# tokyo.net
KiCad netlist of a schematic drawn in EAGLE
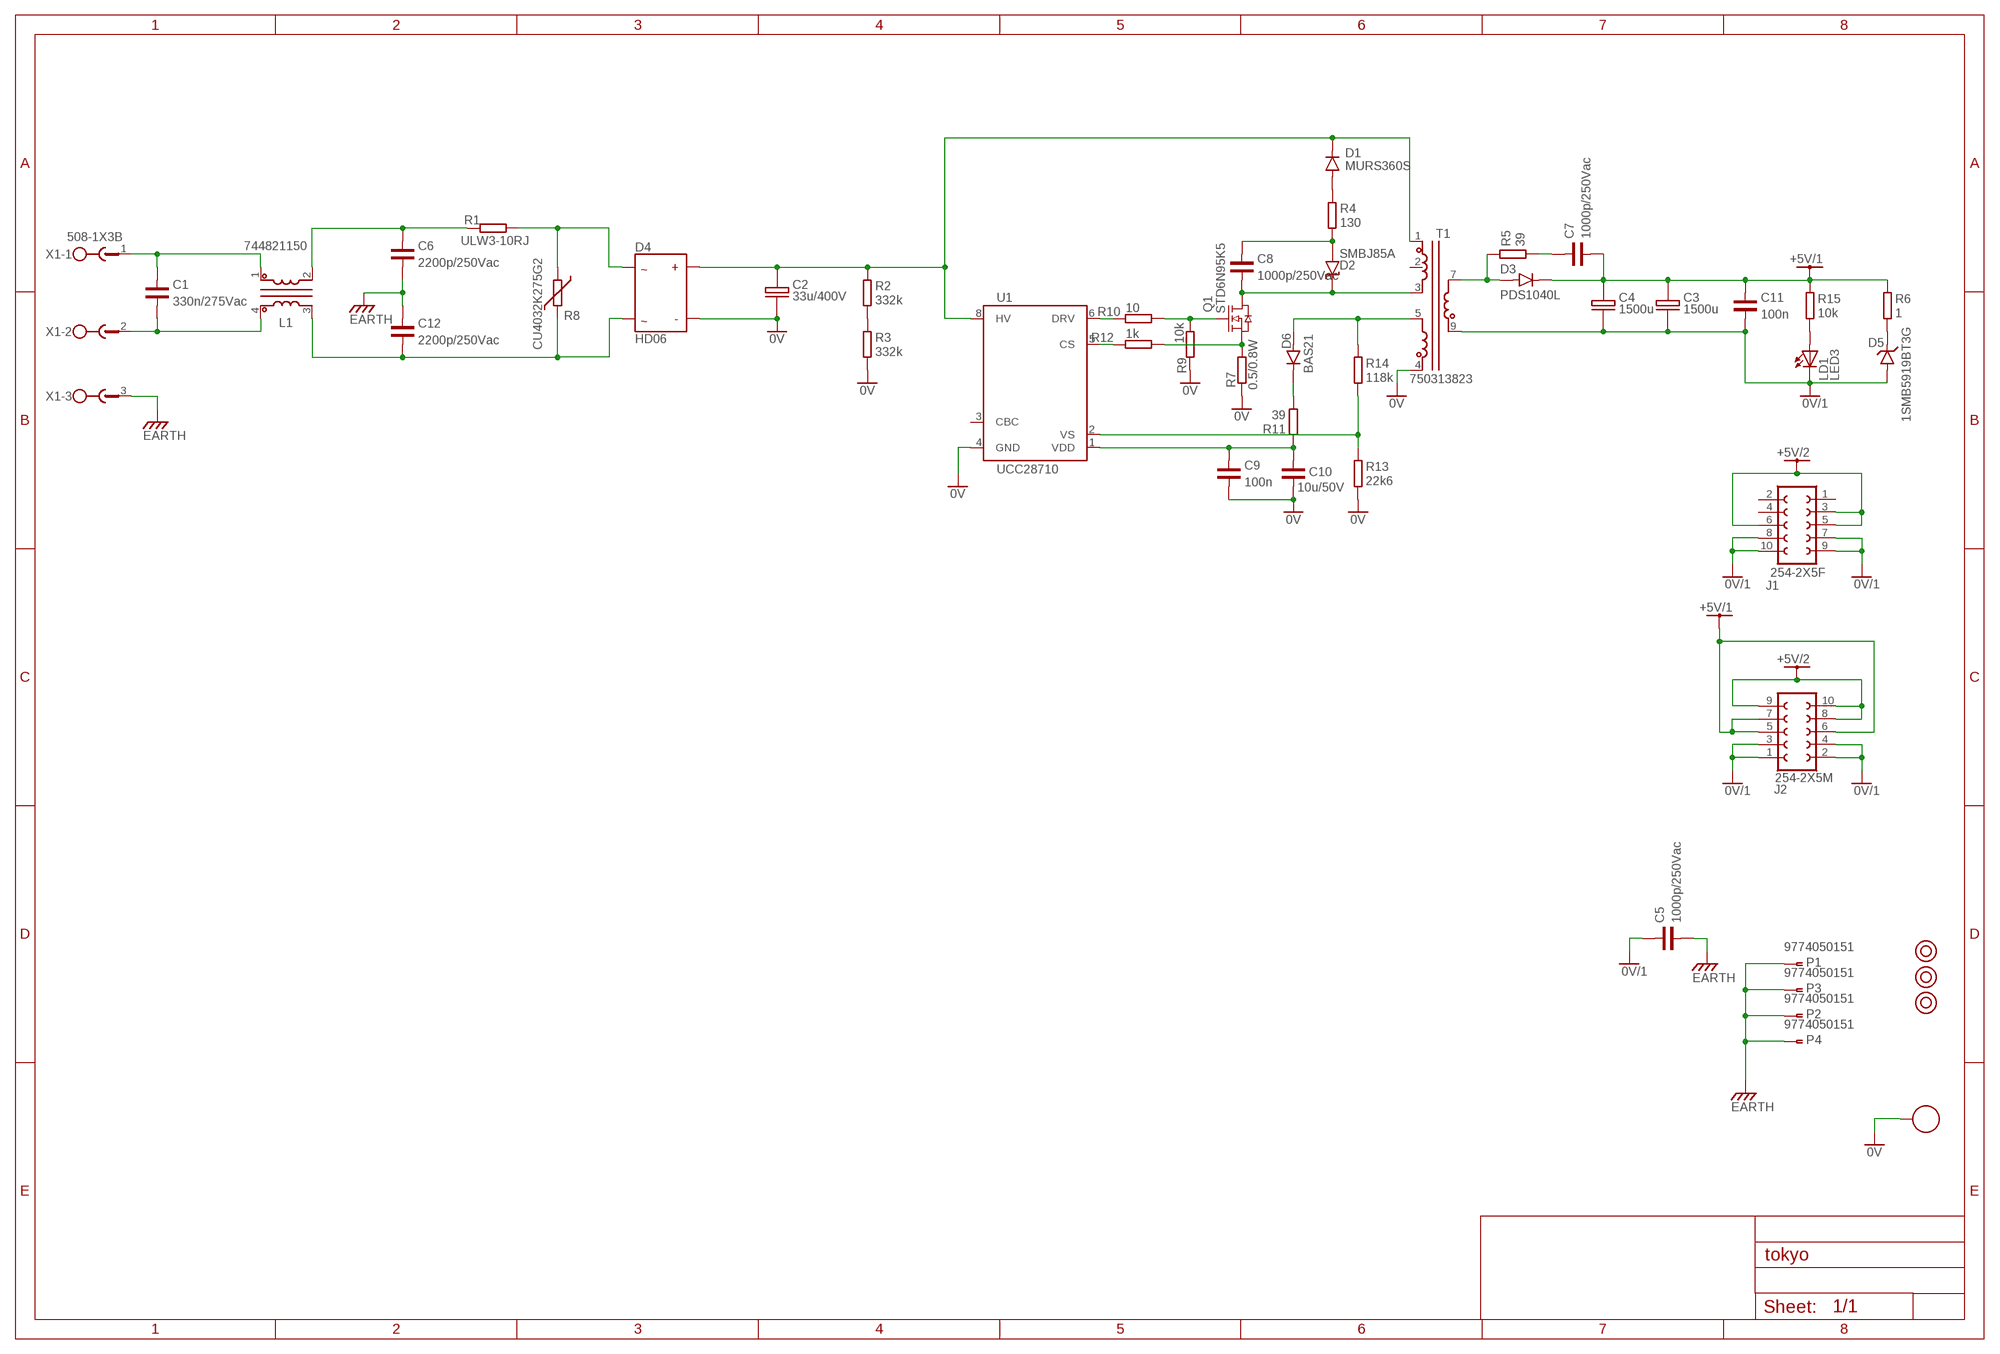
[diagram p0: schematic, sheet 1]

(export (version "E")
  (design (tool "Eeschema 10.0.6"))
  (components
    (comp (ref "0V")
      (value "TESTPOINT")
      (footprint "eagle-import:TESTPOINT")
      (fields (field (name "MF") "Kobiconn"))
      (libsource (lib "eagle-import") (part "TESTPOINT"))
    )
    (comp (ref "C1")
      (value "330n/275Vac")
      (footprint "eagle-import:15X8.5")
      (libsource (lib "eagle-import") (part "C15X8.5"))
    )
    (comp (ref "C2")
      (value "33u/400V")
      (footprint "eagle-import:D18")
      (libsource (lib "eagle-import") (part "C+D18"))
    )
    (comp (ref "C3")
      (value "1500u")
      (footprint "eagle-import:D10")
      (libsource (lib "eagle-import") (part "C+D10"))
    )
    (comp (ref "C4")
      (value "1500u")
      (footprint "eagle-import:D10")
      (libsource (lib "eagle-import") (part "C+D10"))
    )
    (comp (ref "C5")
      (value "1000p/250Vac")
      (footprint "eagle-import:1812")
      (libsource (lib "eagle-import") (part "C1812"))
    )
    (comp (ref "C6")
      (value "2200p/250Vac")
      (footprint "eagle-import:2211")
      (libsource (lib "eagle-import") (part "C2211"))
    )
    (comp (ref "C7")
      (value "1000p/250Vac")
      (footprint "eagle-import:1812")
      (libsource (lib "eagle-import") (part "C1812"))
    )
    (comp (ref "C8")
      (value "1000p/250Vac")
      (footprint "eagle-import:1812")
      (libsource (lib "eagle-import") (part "C1812"))
    )
    (comp (ref "C9")
      (value "100n")
      (footprint "eagle-import:0603")
      (libsource (lib "eagle-import") (part "C0603"))
    )
    (comp (ref "C10")
      (value "10u/50V")
      (footprint "eagle-import:1206")
      (libsource (lib "eagle-import") (part "C1206"))
    )
    (comp (ref "C11")
      (value "100n")
      (footprint "eagle-import:0603")
      (libsource (lib "eagle-import") (part "C0603"))
    )
    (comp (ref "C12")
      (value "2200p/250Vac")
      (footprint "eagle-import:2211")
      (libsource (lib "eagle-import") (part "C2211"))
    )
    (comp (ref "D1")
      (value "MURS360S")
      (footprint "eagle-import:DO-214AA")
      (fields (field (name "MF") "Vishay"))
      (libsource (lib "eagle-import") (part "MURS360S"))
    )
    (comp (ref "D2")
      (value "SMBJ85A")
      (footprint "eagle-import:DO-214AA")
      (fields (field (name "MF") "Bourns"))
      (libsource (lib "eagle-import") (part "SMBJ85A"))
    )
    (comp (ref "D3")
      (value "PDS1040L")
      (footprint "eagle-import:POWERDI5")
      (fields (field (name "MF") "Diodes Inc."))
      (libsource (lib "eagle-import") (part "PDS1040L"))
    )
    (comp (ref "D4")
      (value "HD06")
      (footprint "eagle-import:MINIDIP")
      (fields (field (name "MF") "Diodes Inc."))
      (libsource (lib "eagle-import") (part "HD06"))
    )
    (comp (ref "D5")
      (value "1SMB5919BT3G")
      (footprint "eagle-import:DO-214AA")
      (fields (field (name "MF") "ON Semiconductor"))
      (libsource (lib "eagle-import") (part "1SMB5919BT3G"))
    )
    (comp (ref "D6")
      (value "BAS21")
      (footprint "eagle-import:SOT23")
      (fields (field (name "MF") "Fairchild"))
      (libsource (lib "eagle-import") (part "BAS21"))
    )
    (comp (ref "FIDUCIAL1")
      (value "FIDUCIAL")
      (footprint "eagle-import:FIDUCIAL")
      (libsource (lib "eagle-import") (part "FIDUCIAL"))
    )
    (comp (ref "FIDUCIAL2")
      (value "FIDUCIAL")
      (footprint "eagle-import:FIDUCIAL")
      (libsource (lib "eagle-import") (part "FIDUCIAL"))
    )
    (comp (ref "FIDUCIAL3")
      (value "FIDUCIAL")
      (footprint "eagle-import:FIDUCIAL")
      (libsource (lib "eagle-import") (part "FIDUCIAL"))
    )
    (comp (ref "J1")
      (value "254-2X5F")
      (footprint "eagle-import:254-2X5F")
      (fields (field (name "MF") "Würth Elektronik"))
      (libsource (lib "eagle-import") (part "254-2X5F"))
    )
    (comp (ref "J2")
      (value "254-2X5M")
      (footprint "eagle-import:254-2X5M")
      (fields (field (name "MF") "Würth Elektronik"))
      (libsource (lib "eagle-import") (part "254-2X5M"))
    )
    (comp (ref "L1")
      (value "744821150")
      (footprint "eagle-import:744821150")
      (fields (field (name "MF") "Würth Elektronik"))
      (libsource (lib "eagle-import") (part "744821150"))
    )
    (comp (ref "LD1")
      (value "LED3")
      (footprint "eagle-import:LED3")
      (libsource (lib "eagle-import") (part "LED3"))
    )
    (comp (ref "P1")
      (value "9774050151")
      (footprint "eagle-import:9774050151")
      (fields (field (name "MF") "Würth Elektronik"))
      (libsource (lib "eagle-import") (part "9774050151"))
    )
    (comp (ref "P2")
      (value "9774050151")
      (footprint "eagle-import:9774050151")
      (fields (field (name "MF") "Würth Elektronik"))
      (libsource (lib "eagle-import") (part "9774050151"))
    )
    (comp (ref "P3")
      (value "9774050151")
      (footprint "eagle-import:9774050151")
      (fields (field (name "MF") "Würth Elektronik"))
      (libsource (lib "eagle-import") (part "9774050151"))
    )
    (comp (ref "P4")
      (value "9774050151")
      (footprint "eagle-import:9774050151")
      (fields (field (name "MF") "Würth Elektronik"))
      (libsource (lib "eagle-import") (part "9774050151"))
    )
    (comp (ref "Q1")
      (value "STD6N95K5")
      (footprint "eagle-import:DPAK")
      (fields (field (name "MF") "ST Microelectronics"))
      (libsource (lib "eagle-import") (part "STD6N95K5"))
    )
    (comp (ref "R1")
      (value "ULW3-10RJ")
      (footprint "eagle-import:15X6")
      (libsource (lib "eagle-import") (part "R15X6"))
    )
    (comp (ref "R2")
      (value "332k")
      (footprint "eagle-import:1206")
      (libsource (lib "eagle-import") (part "R1206"))
    )
    (comp (ref "R3")
      (value "332k")
      (footprint "eagle-import:1206")
      (libsource (lib "eagle-import") (part "R1206"))
    )
    (comp (ref "R4")
      (value "130")
      (footprint "eagle-import:1206")
      (libsource (lib "eagle-import") (part "R1206"))
    )
    (comp (ref "R5")
      (value "39")
      (footprint "eagle-import:1206")
      (libsource (lib "eagle-import") (part "R1206"))
    )
    (comp (ref "R6")
      (value "1")
      (footprint "eagle-import:1206")
      (libsource (lib "eagle-import") (part "R1206"))
    )
    (comp (ref "R7")
      (value "0.5/0.8W")
      (footprint "eagle-import:2512")
      (libsource (lib "eagle-import") (part "R2512"))
    )
    (comp (ref "R8")
      (value "CU4032K275G2")
      (footprint "eagle-import:4032")
      (libsource (lib "eagle-import") (part "CU4032K275G2"))
    )
    (comp (ref "R9")
      (value "10k")
      (footprint "eagle-import:0603")
      (libsource (lib "eagle-import") (part "R0603"))
    )
    (comp (ref "R10")
      (value "10")
      (footprint "eagle-import:0603")
      (libsource (lib "eagle-import") (part "R0603"))
    )
    (comp (ref "R11")
      (value "39")
      (footprint "eagle-import:0603")
      (libsource (lib "eagle-import") (part "R0603"))
    )
    (comp (ref "R12")
      (value "1k")
      (footprint "eagle-import:0603")
      (libsource (lib "eagle-import") (part "R0603"))
    )
    (comp (ref "R13")
      (value "22k6")
      (footprint "eagle-import:0603")
      (libsource (lib "eagle-import") (part "R0603"))
    )
    (comp (ref "R14")
      (value "118k")
      (footprint "eagle-import:0603")
      (libsource (lib "eagle-import") (part "R0603"))
    )
    (comp (ref "R15")
      (value "10k")
      (footprint "eagle-import:0603")
      (libsource (lib "eagle-import") (part "R0603"))
    )
    (comp (ref "T1")
      (value "750313823")
      (footprint "eagle-import:EE16")
      (fields (field (name "MF") "Würth Elektronik"))
      (libsource (lib "eagle-import") (part "750313823"))
    )
    (comp (ref "U1")
      (value "UCC28710")
      (footprint "eagle-import:SOIC7")
      (fields (field (name "MF") "Texas Instruments"))
      (libsource (lib "eagle-import") (part "UCC28710"))
    )
    (comp (ref "X1")
      (value "508-1X3B")
      (footprint "eagle-import:508-1X3B")
      (fields (field (name "MF") "Würth Elektronik"))
      (libsource (lib "eagle-import") (part "508-1X3B"))
    )
  )
  (nets
    (net (code "1") (name "+5V{slash}1") (class "Default")
      (node (ref "C11") (pin "1") (pinfunction "1_1") (pintype "passive"))
      (node (ref "C3") (pin "1") (pinfunction "1_1") (pintype "passive"))
      (node (ref "C4") (pin "1") (pinfunction "1_1") (pintype "passive"))
      (node (ref "C7") (pin "2") (pinfunction "2_2") (pintype "passive"))
      (node (ref "D3") (pin "3") (pinfunction "1_3") (pintype "passive"))
      (node (ref "J2") (pin "5") (pinfunction "5_5") (pintype "passive"))
      (node (ref "J2") (pin "6") (pinfunction "6_6") (pintype "passive"))
      (node (ref "J2") (pin "7") (pinfunction "7_7") (pintype "passive"))
      (node (ref "R15") (pin "1") (pinfunction "1_1") (pintype "passive"))
      (node (ref "R6") (pin "1") (pinfunction "1_1") (pintype "passive"))
    )
    (net (code "2") (name "+5V{slash}2") (class "Default")
      (node (ref "J1") (pin "3") (pinfunction "3_3") (pintype "passive"))
      (node (ref "J1") (pin "5") (pinfunction "5_5") (pintype "passive"))
      (node (ref "J1") (pin "6") (pinfunction "6_6") (pintype "passive"))
      (node (ref "J2") (pin "10") (pinfunction "10_10") (pintype "passive"))
      (node (ref "J2") (pin "8") (pinfunction "8_8") (pintype "passive"))
      (node (ref "J2") (pin "9") (pinfunction "9_9") (pintype "passive"))
    )
    (net (code "3") (name "0V") (class "Default")
      (node (ref "0V") (pin "P$1") (pinfunction "P$1_P$1") (pintype "bidirectional"))
      (node (ref "C10") (pin "2") (pinfunction "2_2") (pintype "passive"))
      (node (ref "C2") (pin "2") (pinfunction "2_2") (pintype "passive"))
      (node (ref "C9") (pin "2") (pinfunction "2_2") (pintype "passive"))
      (node (ref "D4") (pin "2") (pinfunction "2_2") (pintype "output"))
      (node (ref "R13") (pin "2") (pinfunction "2_2") (pintype "passive"))
      (node (ref "R3") (pin "2") (pinfunction "2_2") (pintype "passive"))
      (node (ref "R7") (pin "1") (pinfunction "1_1") (pintype "passive"))
      (node (ref "R9") (pin "1") (pinfunction "1_1") (pintype "passive"))
      (node (ref "T1") (pin "4") (pinfunction "4_4") (pintype "bidirectional"))
      (node (ref "U1") (pin "4") (pinfunction "GND_4") (pintype "power_in"))
    )
    (net (code "4") (name "0V{slash}1") (class "Default")
      (node (ref "C11") (pin "2") (pinfunction "2_2") (pintype "passive"))
      (node (ref "C3") (pin "2") (pinfunction "2_2") (pintype "passive"))
      (node (ref "C4") (pin "2") (pinfunction "2_2") (pintype "passive"))
      (node (ref "C5") (pin "1") (pinfunction "1_1") (pintype "passive"))
      (node (ref "D5") (pin "2") (pinfunction "2_2") (pintype "passive"))
      (node (ref "J1") (pin "10") (pinfunction "10_10") (pintype "passive"))
      (node (ref "J1") (pin "7") (pinfunction "7_7") (pintype "passive"))
      (node (ref "J1") (pin "8") (pinfunction "8_8") (pintype "passive"))
      (node (ref "J1") (pin "9") (pinfunction "9_9") (pintype "passive"))
      (node (ref "J2") (pin "1") (pinfunction "1_1") (pintype "passive"))
      (node (ref "J2") (pin "2") (pinfunction "2_2") (pintype "passive"))
      (node (ref "J2") (pin "3") (pinfunction "3_3") (pintype "passive"))
      (node (ref "J2") (pin "4") (pinfunction "4_4") (pintype "passive"))
      (node (ref "LD1") (pin "C") (pinfunction "C_C") (pintype "passive"))
      (node (ref "T1") (pin "9") (pinfunction "9_9") (pintype "bidirectional"))
    )
    (net (code "5") (name "EARTH") (class "Default")
      (node (ref "C12") (pin "2") (pinfunction "1_2") (pintype "passive"))
      (node (ref "C5") (pin "2") (pinfunction "2_2") (pintype "passive"))
      (node (ref "C6") (pin "1") (pinfunction "2_1") (pintype "passive"))
      (node (ref "P1") (pin "P1") (pinfunction "1_P1") (pintype "passive"))
      (node (ref "P2") (pin "P1") (pinfunction "1_P1") (pintype "passive"))
      (node (ref "P3") (pin "P1") (pinfunction "1_P1") (pintype "passive"))
      (node (ref "P4") (pin "P1") (pinfunction "1_P1") (pintype "passive"))
      (node (ref "X1") (pin "3") (pinfunction "1_3") (pintype "passive"))
    )
    (net (code "6") (name "Net-(C1-Pad1)") (class "Default")
      (node (ref "C1") (pin "1") (pinfunction "1_1") (pintype "passive"))
      (node (ref "L1") (pin "1") (pinfunction "1_1") (pintype "bidirectional"))
      (node (ref "X1") (pin "1") (pinfunction "1_1") (pintype "passive"))
    )
    (net (code "7") (name "Net-(C6-1)") (class "Default")
      (node (ref "C6") (pin "2") (pinfunction "1_2") (pintype "passive"))
      (node (ref "L1") (pin "2") (pinfunction "2_2") (pintype "bidirectional"))
      (node (ref "R1") (pin "1") (pinfunction "1_1") (pintype "passive"))
    )
    (net (code "8") (name "Net-(C7-Pad1)") (class "Default")
      (node (ref "C7") (pin "1") (pinfunction "1_1") (pintype "passive"))
      (node (ref "R5") (pin "2") (pinfunction "2_2") (pintype "passive"))
    )
    (net (code "9") (name "Net-(C12-2)") (class "Default")
      (node (ref "C12") (pin "1") (pinfunction "2_1") (pintype "passive"))
      (node (ref "D4") (pin "4") (pinfunction "4_4") (pintype "input"))
      (node (ref "L1") (pin "3") (pinfunction "3_3") (pintype "bidirectional"))
      (node (ref "R8") (pin "2") (pinfunction "2_2") (pintype "passive"))
    )
    (net (code "10") (name "Net-(D1-Pad2)") (class "Default")
      (node (ref "D1") (pin "2") (pinfunction "2_2") (pintype "passive"))
      (node (ref "R4") (pin "1") (pinfunction "1_1") (pintype "passive"))
    )
    (net (code "11") (name "Net-(D2-A)") (class "Default")
      (node (ref "C8") (pin "1") (pinfunction "1_1") (pintype "passive"))
      (node (ref "D2") (pin "2") (pinfunction "A_2") (pintype "passive"))
      (node (ref "R4") (pin "2") (pinfunction "2_2") (pintype "passive"))
    )
    (net (code "12") (name "Net-(D2-C)") (class "Default")
      (node (ref "C8") (pin "2") (pinfunction "2_2") (pintype "passive"))
      (node (ref "D2") (pin "1") (pinfunction "C_1") (pintype "passive"))
      (node (ref "Q1") (pin "2") (pinfunction "D_2") (pintype "passive"))
      (node (ref "T1") (pin "3") (pinfunction "3_3") (pintype "bidirectional"))
    )
    (net (code "13") (name "Net-(D3-2-Pad1)") (class "Default")
      (node (ref "D3") (pin "1") (pinfunction "2_1") (pintype "passive"))
      (node (ref "D3") (pin "2") (pinfunction "2_2") (pintype "passive"))
      (node (ref "R5") (pin "1") (pinfunction "1_1") (pintype "passive"))
      (node (ref "T1") (pin "7") (pinfunction "7_7") (pintype "bidirectional"))
    )
    (net (code "14") (name "Net-(D5-Pad1)") (class "Default")
      (node (ref "D5") (pin "1") (pinfunction "1_1") (pintype "passive"))
      (node (ref "R6") (pin "2") (pinfunction "2_2") (pintype "passive"))
    )
    (net (code "15") (name "Net-(D6-1)") (class "Default")
      (node (ref "D6") (pin "3") (pinfunction "1_3") (pintype "passive"))
      (node (ref "R11") (pin "2") (pinfunction "2_2") (pintype "passive"))
    )
    (net (code "16") (name "Net-(D6-2)") (class "Default")
      (node (ref "D6") (pin "1") (pinfunction "2_1") (pintype "passive"))
      (node (ref "R14") (pin "1") (pinfunction "1_1") (pintype "passive"))
      (node (ref "T1") (pin "5") (pinfunction "5_5") (pintype "bidirectional"))
    )
    (net (code "17") (name "Net-(LD1-PadA)") (class "Default")
      (node (ref "LD1") (pin "A") (pinfunction "A_A") (pintype "passive"))
      (node (ref "R15") (pin "2") (pinfunction "2_2") (pintype "passive"))
    )
    (net (code "18") (name "Net-(Q1-G)") (class "Default")
      (node (ref "Q1") (pin "1") (pinfunction "G_1") (pintype "passive"))
      (node (ref "R10") (pin "2") (pinfunction "2_2") (pintype "passive"))
      (node (ref "R9") (pin "2") (pinfunction "2_2") (pintype "passive"))
    )
    (net (code "19") (name "Net-(Q1-S)") (class "Default")
      (node (ref "Q1") (pin "3") (pinfunction "S_3") (pintype "passive"))
      (node (ref "R12") (pin "2") (pinfunction "2_2") (pintype "passive"))
      (node (ref "R7") (pin "2") (pinfunction "2_2") (pintype "passive"))
    )
    (net (code "20") (name "Net-(R1-2)") (class "Default")
      (node (ref "D4") (pin "3") (pinfunction "3_3") (pintype "input"))
      (node (ref "R1") (pin "P$2") (pinfunction "2_P$2") (pintype "passive"))
      (node (ref "R8") (pin "1") (pinfunction "1_1") (pintype "passive"))
    )
    (net (code "21") (name "Net-(R2-Pad2)") (class "Default")
      (node (ref "R2") (pin "2") (pinfunction "2_2") (pintype "passive"))
      (node (ref "R3") (pin "1") (pinfunction "1_1") (pintype "passive"))
    )
    (net (code "22") (name "Net-(U1-CS)") (class "Default")
      (node (ref "R12") (pin "1") (pinfunction "1_1") (pintype "passive"))
      (node (ref "U1") (pin "5") (pinfunction "CS_5") (pintype "input"))
    )
    (net (code "23") (name "Net-(U1-DRV)") (class "Default")
      (node (ref "R10") (pin "1") (pinfunction "1_1") (pintype "passive"))
      (node (ref "U1") (pin "6") (pinfunction "DRV_6") (pintype "output"))
    )
    (net (code "24") (name "Net-(U1-HV)") (class "Default")
      (node (ref "C2") (pin "1") (pinfunction "1_1") (pintype "passive"))
      (node (ref "D1") (pin "1") (pinfunction "1_1") (pintype "passive"))
      (node (ref "D4") (pin "1") (pinfunction "1_1") (pintype "output"))
      (node (ref "R2") (pin "1") (pinfunction "1_1") (pintype "passive"))
      (node (ref "T1") (pin "1") (pinfunction "1_1") (pintype "bidirectional"))
      (node (ref "U1") (pin "8") (pinfunction "HV_8") (pintype "input"))
    )
    (net (code "25") (name "Net-(U1-VDD)") (class "Default")
      (node (ref "C10") (pin "1") (pinfunction "1_1") (pintype "passive"))
      (node (ref "C9") (pin "1") (pinfunction "1_1") (pintype "passive"))
      (node (ref "R11") (pin "1") (pinfunction "1_1") (pintype "passive"))
      (node (ref "U1") (pin "1") (pinfunction "VDD_1") (pintype "input"))
    )
    (net (code "26") (name "Net-(U1-VS)") (class "Default")
      (node (ref "R13") (pin "1") (pinfunction "1_1") (pintype "passive"))
      (node (ref "R14") (pin "2") (pinfunction "2_2") (pintype "passive"))
      (node (ref "U1") (pin "2") (pinfunction "VS_2") (pintype "input"))
    )
    (net (code "27") (name "Net-(X1B-1)") (class "Default")
      (node (ref "C1") (pin "2") (pinfunction "2_2") (pintype "passive"))
      (node (ref "L1") (pin "4") (pinfunction "4_4") (pintype "bidirectional"))
      (node (ref "X1") (pin "2") (pinfunction "1_2") (pintype "passive"))
    )
    (net (code "28") (name "unconnected-(J1-Pad1)") (class "Default")
      (node (ref "J1") (pin "1") (pinfunction "1_1") (pintype "passive"))
    )
    (net (code "29") (name "unconnected-(J1-Pad2)") (class "Default")
      (node (ref "J1") (pin "2") (pinfunction "2_2") (pintype "passive"))
    )
    (net (code "30") (name "unconnected-(J1-Pad4)") (class "Default")
      (node (ref "J1") (pin "4") (pinfunction "4_4") (pintype "passive"))
    )
    (net (code "31") (name "unconnected-(T1-Pad2)") (class "Default")
      (node (ref "T1") (pin "2") (pinfunction "2_2") (pintype "bidirectional"))
    )
    (net (code "32") (name "unconnected-(U1-CBC-Pad3)") (class "Default")
      (node (ref "U1") (pin "3") (pinfunction "CBC_3") (pintype "input"))
    )
  )
)
